# SCH_BTL.net
KiCad netlist of a schematic drawn in Altium Designer
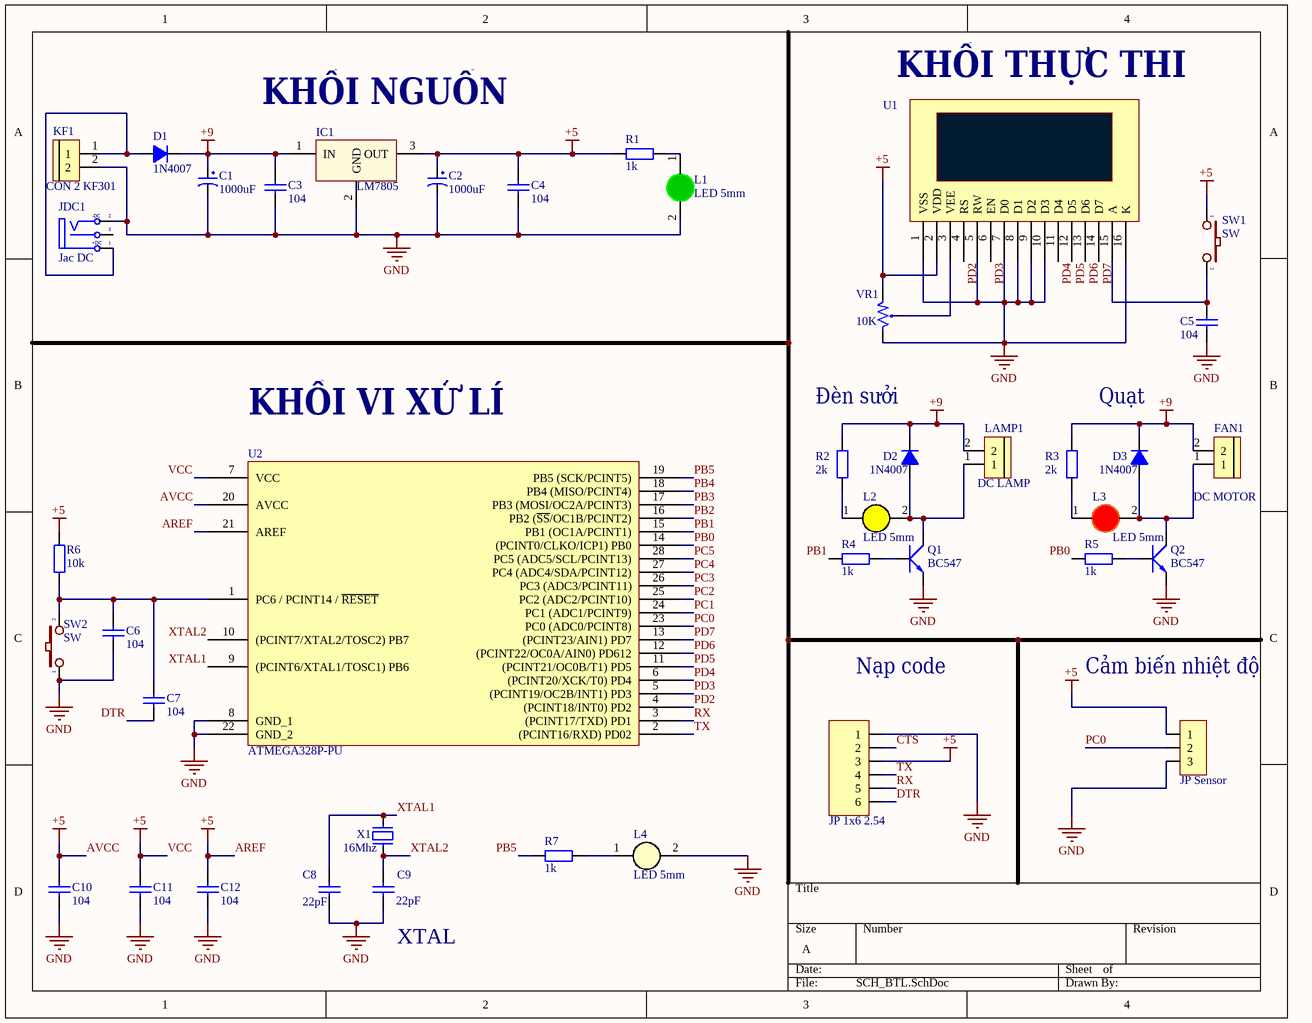
[diagram p0: SCH_BTL.SchDoc]

(export (version "E")
  (design (tool "Eeschema 10.0.6"))
  (components
    (comp (ref "C1")
      (value "1000uF")
      (footprint "tu hoa 8mm")
      (description "Cắm")
      (libsource (lib "Capacitor") (part "Tu Hoa 1000uF 16V 8x20"))
    )
    (comp (ref "C2")
      (value "1000uF")
      (footprint "tu hoa 8mm")
      (description "Cắm")
      (libsource (lib "Capacitor") (part "Tu Hoa 1000uF 16V 8x20"))
    )
    (comp (ref "C3")
      (value "104")
      (footprint "tu gom")
      (description "Cắm")
      (libsource (lib "Capacitor") (part "Tu gom 104 50V"))
    )
    (comp (ref "C4")
      (value "104")
      (footprint "tu gom")
      (description "Cắm")
      (libsource (lib "Capacitor") (part "Tu gom 104 50V"))
    )
    (comp (ref "C5")
      (value "104")
      (footprint "tu gom")
      (description "Cắm")
      (libsource (lib "Capacitor") (part "Tu gom 101 50V"))
    )
    (comp (ref "C6")
      (value "104")
      (footprint "tu gom")
      (description "Cắm")
      (libsource (lib "Capacitor") (part "Tu gom 101 50V"))
    )
    (comp (ref "C7")
      (value "104")
      (footprint "tu gom")
      (description "Cắm")
      (libsource (lib "Capacitor") (part "Tu gom 104 50V"))
    )
    (comp (ref "C8")
      (value "22pF")
      (footprint "tu gom")
      (description "Cắm")
      (libsource (lib "Capacitor") (part "Tu gom 22pF 50V"))
    )
    (comp (ref "C9")
      (value "22pF")
      (footprint "tu gom")
      (description "Cắm")
      (libsource (lib "Capacitor") (part "Tu gom 22pF 50V"))
    )
    (comp (ref "C10")
      (value "104")
      (footprint "tu gom")
      (description "Cắm")
      (libsource (lib "Capacitor") (part "Tu gom 101 50V"))
    )
    (comp (ref "C11")
      (value "104")
      (footprint "tu gom")
      (description "Cắm")
      (libsource (lib "Capacitor") (part "Tu gom 101 50V"))
    )
    (comp (ref "C12")
      (value "104")
      (footprint "tu gom")
      (description "Cắm")
      (libsource (lib "Capacitor") (part "Tu gom 101 50V"))
    )
    (comp (ref "D1")
      (value "1N4007")
      (footprint "D1A")
      (description "Diode 1A")
      (libsource (lib "Cty1") (part "D1A"))
    )
    (comp (ref "D2")
      (value "1N4007")
      (footprint "D1A")
      (description "Diode 1A")
      (libsource (lib "Cty1") (part "D1A"))
    )
    (comp (ref "D3")
      (value "1N4007")
      (footprint "D1A")
      (description "Diode 1A")
      (libsource (lib "Cty1") (part "D1A"))
    )
    (comp (ref "FAN1")
      (value "DC MOTOR")
      (footprint "Con 2 KF301 5.08")
      (description "Cắm")
      (libsource (lib "Connector") (part "CON 2 KF301"))
    )
    (comp (ref "IC1")
      (value "LM7805")
      (footprint "QTO-220")
      (description "On ap +, from + 5 to + 24VDC")
      (libsource (lib "Cty1") (part "LM78xx"))
    )
    (comp (ref "JDC1")
      (value "Jac DC")
      (footprint "DC-IN")
      (description "Jac DC input")
      (libsource (lib "Cty1") (part "DCIN"))
    )
    (comp (ref "JP1")
      (value "JP 1x6 2.54")
      (footprint "JP 1x6 CC")
      (description "Cắm")
      (libsource (lib "Jump") (part "JP 1x6 2.54 Cai Cong"))
    )
    (comp (ref "JP2")
      (value "JP Sensor")
      (footprint "JP 1x3 CT")
      (description "Cắm")
      (libsource (lib "Jump") (part "JP 1x3 2.54 Cai Thang"))
    )
    (comp (ref "KF1")
      (value "CON 2 KF301")
      (footprint "Con 2 KF301 5.08")
      (description "Cắm")
      (libsource (lib "") (part "CON 2 KF301_1"))
    )
    (comp (ref "L1")
      (value "LED 5mm")
      (footprint "LED-5MM-Green")
      (description "Cắm")
      (libsource (lib "Led") (part "LED 5mm Xanh La"))
    )
    (comp (ref "L2")
      (value "LED 5mm")
      (footprint "LED-5MM-Yellow")
      (description "Cắm")
      (libsource (lib "Led") (part "LED 5mm Vang"))
    )
    (comp (ref "L3")
      (value "LED 5mm")
      (footprint "LED-5MM-RED")
      (description "Cắm")
      (libsource (lib "Led") (part "LED 5mm Do"))
    )
    (comp (ref "L4")
      (value "LED 5mm")
      (footprint "LED-5MM-WHITE")
      (description "Cắm")
      (libsource (lib "Led") (part "LED 5mm Trang"))
    )
    (comp (ref "LAMP1")
      (value "DC LAMP")
      (footprint "Con 2 KF301 5.08")
      (description "Cắm")
      (libsource (lib "Connector") (part "CON 2 KF301"))
    )
    (comp (ref "Q1")
      (value "BC547")
      (footprint "TO92")
      (description "NPN transistor EBC")
      (libsource (lib "TranFet") (part "Trans 2N3904"))
    )
    (comp (ref "Q2")
      (value "BC547")
      (footprint "TO92")
      (description "NPN transistor EBC")
      (libsource (lib "TranFet") (part "Trans 2N3904"))
    )
    (comp (ref "R1")
      (value "1k")
      (footprint "tro vach 1/4w")
      (description "Cắm")
      (libsource (lib "Resistor") (part "Tro Vach 1/4W 5% 1k"))
    )
    (comp (ref "R2")
      (value "2k")
      (footprint "tro vach 1/4w")
      (description "Cắm")
      (libsource (lib "Resistor") (part "Tro Vach 1/4W 5% 1k"))
    )
    (comp (ref "R3")
      (value "2k")
      (footprint "tro vach 1/4w")
      (description "Cắm")
      (libsource (lib "Resistor") (part "Tro Vach 1/4W 5% 1k"))
    )
    (comp (ref "R4")
      (value "1k")
      (footprint "tro vach 1/4w")
      (description "Cắm")
      (libsource (lib "Resistor") (part "Tro Vach 1/4W 5% 1k"))
    )
    (comp (ref "R5")
      (value "1k")
      (footprint "tro vach 1/4w")
      (description "Cắm")
      (libsource (lib "Resistor") (part "Tro Vach 1/4W 5% 1k"))
    )
    (comp (ref "R6")
      (value "10k")
      (footprint "tro vach 1/4w")
      (description "Căm")
      (libsource (lib "Resistor") (part "Tro Vach 1/4W 5% 10k"))
    )
    (comp (ref "R7")
      (value "1k")
      (footprint "tro vach 1/4w")
      (description "Cắm")
      (libsource (lib "Resistor") (part "Tro Vach 1/4W 5% 1k"))
    )
    (comp (ref "SW1")
      (value "SW")
      (footprint "SW2")
      (description "Switch button 2 pin")
      (libsource (lib "Cty1") (part "SW2"))
    )
    (comp (ref "SW2")
      (value "SW")
      (footprint "SW2")
      (description "Switch button 2 pin")
      (libsource (lib "Cty1") (part "SW2"))
    )
    (comp (ref "U1") (value "LCD") (footprint "LCD16X2") (libsource (lib "Cty1") (part "LCD")))
    (comp (ref "U2")
      (value "ATMEGA328P-PU")
      (footprint "27_DIP_7.62mm")
      (description "ATMEGA328P-PU; 8 bit Microcontroller AVR 20MHz 1; 32kb Flash; 2kb RAM; I2C SPI 2")
      (fields (field (name "MANUFACTURER") "Microchip / Atmel"))
      (libsource (lib "ATMEGA328P-PU") (part "ATMEGA328P-PU"))
    )
    (comp (ref "VR1")
      (value "10K")
      (footprint "VR1")
      (description "Var Resistor")
      (libsource (lib "syhaunguyen") (part "VR1"))
    )
    (comp (ref "X1")
      (value "16Mhz")
      (footprint "XT2")
      (description "Crystal For all Crystal 2pin.")
      (libsource (lib "syhaunguyen") (part "XT2"))
    )
  )
  (nets
    (net (code "1") (name "+5") (class "Default")
      (node (ref "C10") (pin "1") (pinfunction "1_1") (pintype "passive"))
      (node (ref "C11") (pin "1") (pinfunction "1_1") (pintype "passive"))
      (node (ref "C12") (pin "1") (pinfunction "1_1") (pintype "passive"))
      (node (ref "C2") (pin "1") (pinfunction "1_1") (pintype "passive"))
      (node (ref "C4") (pin "1") (pinfunction "1_1") (pintype "passive"))
      (node (ref "IC1") (pin "3") (pinfunction "OUT_3") (pintype "passive"))
      (node (ref "JP1") (pin "3") (pinfunction "3_3") (pintype "passive"))
      (node (ref "JP2") (pin "1") (pinfunction "1_1") (pintype "passive"))
      (node (ref "R1") (pin "2") (pinfunction "2_2") (pintype "passive"))
      (node (ref "R6") (pin "2") (pinfunction "2_2") (pintype "passive"))
      (node (ref "SW1") (pin "1") (pinfunction "1_1") (pintype "passive"))
      (node (ref "U1") (pin "2") (pinfunction "VDD_2") (pintype "passive"))
      (node (ref "U2") (pin "20") (pinfunction "AVCC_20") (pintype "passive"))
      (node (ref "U2") (pin "21") (pinfunction "AREF_21") (pintype "passive"))
      (node (ref "U2") (pin "7") (pinfunction "VCC_7") (pintype "passive"))
      (node (ref "VR1") (pin "1") (pinfunction "1_1") (pintype "passive"))
    )
    (net (code "2") (name "+9") (class "Default")
      (node (ref "C1") (pin "1") (pinfunction "1_1") (pintype "passive"))
      (node (ref "C3") (pin "1") (pinfunction "1_1") (pintype "passive"))
      (node (ref "D1") (pin "2") (pinfunction "K_2") (pintype "passive"))
      (node (ref "D2") (pin "2") (pinfunction "K_2") (pintype "passive"))
      (node (ref "D3") (pin "2") (pinfunction "K_2") (pintype "passive"))
      (node (ref "FAN1") (pin "2") (pinfunction "2_2") (pintype "passive"))
      (node (ref "IC1") (pin "1") (pinfunction "IN_1") (pintype "passive"))
      (node (ref "LAMP1") (pin "2") (pinfunction "2_2") (pintype "passive"))
      (node (ref "R2") (pin "1") (pinfunction "1_1") (pintype "passive"))
      (node (ref "R3") (pin "1") (pinfunction "1_1") (pintype "passive"))
    )
    (net (code "4") (name "/CTS") (class "Default")
      (node (ref "JP1") (pin "2") (pinfunction "2_2") (pintype "passive"))
    )
    (net (code "5") (name "/DTR") (class "Default")
      (node (ref "C7") (pin "1") (pinfunction "1_1") (pintype "passive"))
      (node (ref "JP1") (pin "6") (pinfunction "6_6") (pintype "passive"))
    )
    (net (code "6") (name "/PB0") (class "Default")
      (node (ref "R5") (pin "1") (pinfunction "1_1") (pintype "passive"))
      (node (ref "U2") (pin "14") (pinfunction "(PCINT0/CLKO/ICP1)_PB0_14") (pintype "passive"))
    )
    (net (code "7") (name "/PB1") (class "Default")
      (node (ref "R4") (pin "1") (pinfunction "1_1") (pintype "passive"))
      (node (ref "U2") (pin "15") (pinfunction "PB1_(OC1A/PCINT1)_15") (pintype "passive"))
    )
    (net (code "8") (name "/PB2") (class "Default")
      (node (ref "U2") (pin "16") (pinfunction "PB2_(~{SS}/OC1B/PCINT2)_16") (pintype "passive"))
    )
    (net (code "9") (name "/PB3") (class "Default")
      (node (ref "U2") (pin "17") (pinfunction "PB3_(MOSI/OC2A/PCINT3)_17") (pintype "passive"))
    )
    (net (code "10") (name "/PB4") (class "Default")
      (node (ref "U2") (pin "18") (pinfunction "PB4_(MISO/PCINT4)_18") (pintype "passive"))
    )
    (net (code "11") (name "/PB5") (class "Default")
      (node (ref "R7") (pin "2") (pinfunction "2_2") (pintype "passive"))
      (node (ref "U2") (pin "19") (pinfunction "PB5_(SCK/PCINT5)_19") (pintype "passive"))
    )
    (net (code "12") (name "/PC0") (class "Default")
      (node (ref "JP2") (pin "2") (pinfunction "2_2") (pintype "passive"))
      (node (ref "U2") (pin "23") (pinfunction "PC0_(ADC0/PCINT8)_23") (pintype "passive"))
    )
    (net (code "13") (name "/PC1") (class "Default")
      (node (ref "U2") (pin "24") (pinfunction "PC1_(ADC1/PCINT9)_24") (pintype "passive"))
    )
    (net (code "14") (name "/PC2") (class "Default")
      (node (ref "U2") (pin "25") (pinfunction "PC2_(ADC2/PCINT10)_25") (pintype "passive"))
    )
    (net (code "15") (name "/PC3") (class "Default")
      (node (ref "U2") (pin "26") (pinfunction "PC3_(ADC3/PCINT11)_26") (pintype "passive"))
    )
    (net (code "16") (name "/PC4") (class "Default")
      (node (ref "U2") (pin "27") (pinfunction "PC4_(ADC4/SDA/PCINT12)_27") (pintype "passive"))
    )
    (net (code "17") (name "/PC5") (class "Default")
      (node (ref "U2") (pin "28") (pinfunction "PC5_(ADC5/SCL/PCINT13)_28") (pintype "passive"))
    )
    (net (code "18") (name "/PD2") (class "Default")
      (node (ref "U1") (pin "4") (pinfunction "RS_4") (pintype "passive"))
      (node (ref "U2") (pin "4") (pinfunction "(PCINT18/INT0)_PD2_4") (pintype "passive"))
    )
    (net (code "19") (name "/PD3") (class "Default")
      (node (ref "U1") (pin "6") (pinfunction "EN_6") (pintype "passive"))
      (node (ref "U2") (pin "5") (pinfunction "(PCINT19/OC2B/INT1)_PD3_5") (pintype "passive"))
    )
    (net (code "20") (name "/PD4") (class "Default")
      (node (ref "U1") (pin "11") (pinfunction "D4_11") (pintype "passive"))
      (node (ref "U2") (pin "6") (pinfunction "(PCINT20/XCK/T0)_PD4_6") (pintype "passive"))
    )
    (net (code "21") (name "/PD5") (class "Default")
      (node (ref "U1") (pin "12") (pinfunction "D5_12") (pintype "passive"))
      (node (ref "U2") (pin "11") (pinfunction "(PCINT21/OC0B/T1)_PD5_11") (pintype "passive"))
    )
    (net (code "22") (name "/PD6") (class "Default")
      (node (ref "U1") (pin "13") (pinfunction "D6_13") (pintype "passive"))
      (node (ref "U2") (pin "12") (pinfunction "(PCINT22/OC0A/AIN0)_PD612_12") (pintype "passive"))
    )
    (net (code "23") (name "/PD7") (class "Default")
      (node (ref "U1") (pin "14") (pinfunction "D7_14") (pintype "passive"))
      (node (ref "U2") (pin "13") (pinfunction "(PCINT23/AIN1)_PD7_13") (pintype "passive"))
    )
    (net (code "24") (name "/RX") (class "Default")
      (node (ref "JP1") (pin "5") (pinfunction "5_5") (pintype "passive"))
      (node (ref "U2") (pin "3") (pinfunction "(PCINT17/TXD)_PD1_3") (pintype "passive"))
    )
    (net (code "25") (name "/TX") (class "Default")
      (node (ref "JP1") (pin "4") (pinfunction "4_4") (pintype "passive"))
      (node (ref "U2") (pin "2") (pinfunction "(PCINT16/RXD)_PD02_2") (pintype "passive"))
    )
    (net (code "26") (name "/XTAL1") (class "Default")
      (node (ref "C8") (pin "1") (pinfunction "1_1") (pintype "passive"))
      (node (ref "U2") (pin "9") (pinfunction "(PCINT6/XTAL1/TOSC1)_PB6_9") (pintype "passive"))
      (node (ref "X1") (pin "2") (pinfunction "2_2") (pintype "passive"))
    )
    (net (code "27") (name "/XTAL2") (class "Default")
      (node (ref "C9") (pin "1") (pinfunction "1_1") (pintype "passive"))
      (node (ref "U2") (pin "10") (pinfunction "(PCINT7/XTAL2/TOSC2)_PB7_10") (pintype "passive"))
      (node (ref "X1") (pin "1") (pinfunction "1_1") (pintype "passive"))
    )
    (net (code "28") (name "GND") (class "Default")
      (node (ref "C1") (pin "2") (pinfunction "2_2") (pintype "passive"))
      (node (ref "C10") (pin "2") (pinfunction "2_2") (pintype "passive"))
      (node (ref "C11") (pin "2") (pinfunction "2_2") (pintype "passive"))
      (node (ref "C12") (pin "2") (pinfunction "2_2") (pintype "passive"))
      (node (ref "C2") (pin "2") (pinfunction "2_2") (pintype "passive"))
      (node (ref "C3") (pin "2") (pinfunction "2_2") (pintype "passive"))
      (node (ref "C4") (pin "2") (pinfunction "2_2") (pintype "passive"))
      (node (ref "C5") (pin "2") (pinfunction "2_2") (pintype "passive"))
      (node (ref "C6") (pin "2") (pinfunction "2_2") (pintype "passive"))
      (node (ref "C8") (pin "2") (pinfunction "2_2") (pintype "passive"))
      (node (ref "C9") (pin "2") (pinfunction "2_2") (pintype "passive"))
      (node (ref "IC1") (pin "2") (pinfunction "GND_2") (pintype "passive"))
      (node (ref "JDC1") (pin "2") (pinfunction "TN_2") (pintype "passive"))
      (node (ref "JP1") (pin "1") (pinfunction "1_1") (pintype "passive"))
      (node (ref "JP2") (pin "3") (pinfunction "3_3") (pintype "passive"))
      (node (ref "KF1") (pin "2") (pinfunction "2_2") (pintype "passive"))
      (node (ref "L1") (pin "2") (pinfunction "K_2") (pintype "passive"))
      (node (ref "L4") (pin "2") (pinfunction "K_2") (pintype "passive"))
      (node (ref "Q1") (pin "1") (pinfunction "E_1") (pintype "passive"))
      (node (ref "Q2") (pin "1") (pinfunction "E_1") (pintype "passive"))
      (node (ref "SW2") (pin "1") (pinfunction "1_1") (pintype "passive"))
      (node (ref "U1") (pin "1") (pinfunction "VSS_1") (pintype "passive"))
      (node (ref "U1") (pin "10") (pinfunction "D3_10") (pintype "passive"))
      (node (ref "U1") (pin "16") (pinfunction "K_16") (pintype "passive"))
      (node (ref "U1") (pin "5") (pinfunction "RW_5") (pintype "passive"))
      (node (ref "U1") (pin "7") (pinfunction "D0_7") (pintype "passive"))
      (node (ref "U1") (pin "8") (pinfunction "D1_8") (pintype "passive"))
      (node (ref "U1") (pin "9") (pinfunction "D2_9") (pintype "passive"))
      (node (ref "U2") (pin "22") (pinfunction "GND_2_22") (pintype "passive"))
      (node (ref "U2") (pin "8") (pinfunction "GND_1_8") (pintype "passive"))
      (node (ref "VR1") (pin "3") (pinfunction "3_3") (pintype "passive"))
    )
    (net (code "29") (name "Net-(D1-A)") (class "Default")
      (node (ref "D1") (pin "1") (pinfunction "A_1") (pintype "passive"))
      (node (ref "JDC1") (pin "1") (pinfunction "T_1") (pintype "passive"))
      (node (ref "KF1") (pin "1") (pinfunction "1_1") (pintype "passive"))
    )
    (net (code "30") (name "Net-(D2-A)") (class "Default")
      (node (ref "D2") (pin "1") (pinfunction "A_1") (pintype "passive"))
      (node (ref "L2") (pin "2") (pinfunction "K_2") (pintype "passive"))
      (node (ref "LAMP1") (pin "1") (pinfunction "1_1") (pintype "passive"))
      (node (ref "Q1") (pin "3") (pinfunction "C_3") (pintype "passive"))
    )
    (net (code "31") (name "Net-(D3-A)") (class "Default")
      (node (ref "D3") (pin "1") (pinfunction "A_1") (pintype "passive"))
      (node (ref "FAN1") (pin "1") (pinfunction "1_1") (pintype "passive"))
      (node (ref "L3") (pin "2") (pinfunction "K_2") (pintype "passive"))
      (node (ref "Q2") (pin "3") (pinfunction "C_3") (pintype "passive"))
    )
    (net (code "32") (name "Net-(L1-A)") (class "Default")
      (node (ref "L1") (pin "1") (pinfunction "A_1") (pintype "passive"))
      (node (ref "R1") (pin "1") (pinfunction "1_1") (pintype "passive"))
    )
    (net (code "33") (name "Net-(L2-A)") (class "Default")
      (node (ref "L2") (pin "1") (pinfunction "A_1") (pintype "passive"))
      (node (ref "R2") (pin "2") (pinfunction "2_2") (pintype "passive"))
    )
    (net (code "34") (name "Net-(L3-A)") (class "Default")
      (node (ref "L3") (pin "1") (pinfunction "A_1") (pintype "passive"))
      (node (ref "R3") (pin "2") (pinfunction "2_2") (pintype "passive"))
    )
    (net (code "35") (name "Net-(L4-A)") (class "Default")
      (node (ref "L4") (pin "1") (pinfunction "A_1") (pintype "passive"))
      (node (ref "R7") (pin "1") (pinfunction "1_1") (pintype "passive"))
    )
    (net (code "36") (name "Net-(Q1-B)") (class "Default")
      (node (ref "Q1") (pin "2") (pinfunction "B_2") (pintype "passive"))
      (node (ref "R4") (pin "2") (pinfunction "2_2") (pintype "passive"))
    )
    (net (code "37") (name "Net-(Q2-B)") (class "Default")
      (node (ref "Q2") (pin "2") (pinfunction "B_2") (pintype "passive"))
      (node (ref "R5") (pin "2") (pinfunction "2_2") (pintype "passive"))
    )
    (net (code "38") (name "Net-(U1-A)") (class "Default")
      (node (ref "C5") (pin "1") (pinfunction "1_1") (pintype "passive"))
      (node (ref "SW1") (pin "2") (pinfunction "2_2") (pintype "passive"))
      (node (ref "U1") (pin "15") (pinfunction "A_15") (pintype "passive"))
    )
    (net (code "39") (name "Net-(U1-VEE)") (class "Default")
      (node (ref "U1") (pin "3") (pinfunction "VEE_3") (pintype "passive"))
      (node (ref "VR1") (pin "2") (pinfunction "2_2") (pintype "passive"))
    )
    (net (code "40") (name "Net-(U2-PC6_{slash}_PCINT14_{slash}_~{RESET})") (class "Default")
      (node (ref "C6") (pin "1") (pinfunction "1_1") (pintype "passive"))
      (node (ref "C7") (pin "2") (pinfunction "2_2") (pintype "passive"))
      (node (ref "R6") (pin "1") (pinfunction "1_1") (pintype "passive"))
      (node (ref "SW2") (pin "2") (pinfunction "2_2") (pintype "passive"))
      (node (ref "U2") (pin "1") (pinfunction "PC6_/_PCINT14_/_~{RESET}_1") (pintype "passive"))
    )
    (net (code "41") (name "unconnected-(JDC1-S-Pad3)") (class "Default")
      (node (ref "JDC1") (pin "3") (pinfunction "S_3") (pintype "power_in"))
    )
  )
)
